# NE5532_TDA2030A.net
KiCad netlist of a schematic drawn in Altium Designer
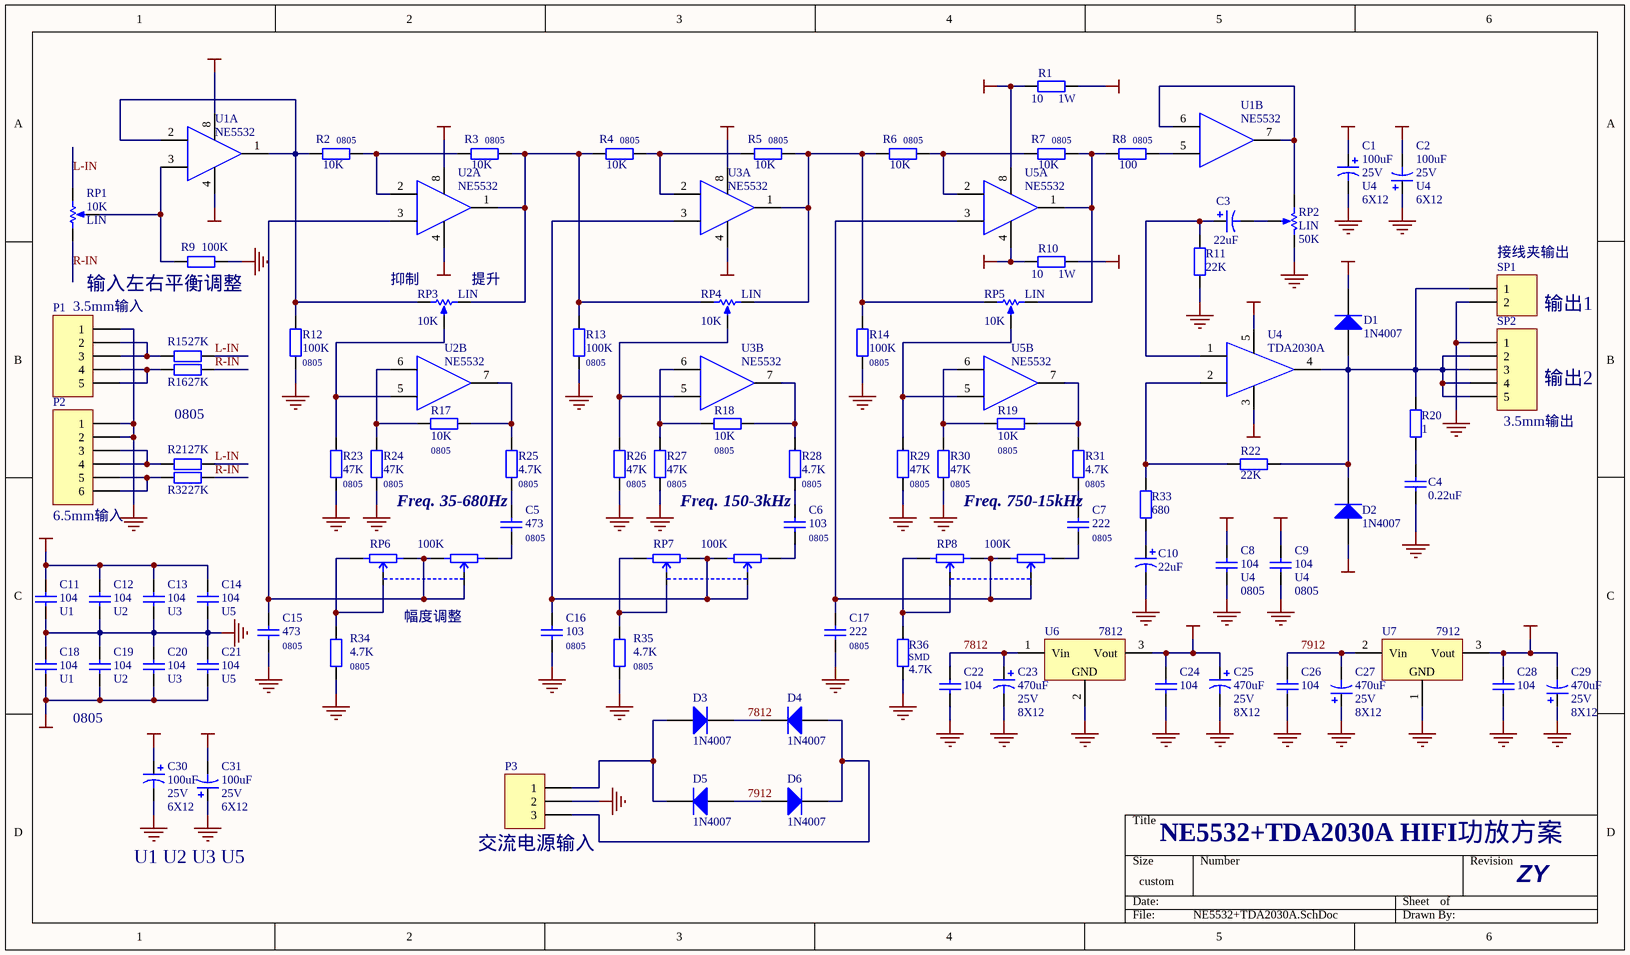
[diagram p0: NE5532+TDA2030A.SchDoc]

(export (version "E")
  (design (tool "Eeschema 10.0.6"))
  (components
    (comp (ref "C1")
      (value "U4")
      (footprint "C 6X12")
      (description "Polarized Capacitor (Radial)")
      (fields
        (field (name "PUBLISHED") "25V")
        (field (name "PUBLISHER") "6X12")
        (field (name "ALTIUM_VALUE") "100uF")
      )
      (libsource (lib "Miscellaneous Devices") (part "Cap Pol1"))
    )
    (comp (ref "C2")
      (value "U4")
      (footprint "C 6X12")
      (description "Polarized Capacitor (Radial)")
      (fields
        (field (name "PUBLISHED") "25V")
        (field (name "PUBLISHER") "6X12")
        (field (name "ALTIUM_VALUE") "100uF")
      )
      (libsource (lib "Miscellaneous Devices") (part "Cap Pol1"))
    )
    (comp (ref "C3")
      (value "22uF")
      (footprint "c1206")
      (description "Polarized Capacitor (Radial)")
      (fields (field (name "Comment") "Cap Pol1") (field (name "PUBLISHER") "Altium Limited"))
      (libsource (lib "Miscellaneous Devices") (part "Cap Pol1"))
    )
    (comp (ref "C4")
      (value "0.22uF")
      (footprint "RAD-0.1")
      (description "Capacitor")
      (fields (field (name "Comment") "Cap") (field (name "PUBLISHER") "Altium Limited"))
      (libsource (lib "Miscellaneous Devices") (part "Cap"))
    )
    (comp (ref "C5")
      (value "473")
      (footprint "c0805")
      (description "Capacitor")
      (fields (field (name "ALTIUM_VALUE") "0805") (field (name "PUBLISHER") "Altium Limited"))
      (libsource (lib "Miscellaneous Devices") (part "Cap"))
    )
    (comp (ref "C6")
      (value "103")
      (footprint "c0805")
      (description "Capacitor")
      (fields (field (name "ALTIUM_VALUE") "0805") (field (name "PUBLISHER") "Altium Limited"))
      (libsource (lib "Miscellaneous Devices") (part "Cap"))
    )
    (comp (ref "C7")
      (value "222")
      (footprint "c0805")
      (description "Capacitor")
      (fields (field (name "ALTIUM_VALUE") "0805") (field (name "PUBLISHER") "Altium Limited"))
      (libsource (lib "Miscellaneous Devices") (part "Cap"))
    )
    (comp (ref "C8")
      (value "U4")
      (footprint "c0805")
      (description "Capacitor")
      (fields (field (name "PUBLISHER") "0805") (field (name "ALTIUM_VALUE") "104"))
      (libsource (lib "Miscellaneous Devices") (part "Cap"))
    )
    (comp (ref "C9")
      (value "U4")
      (footprint "C0805")
      (description "Capacitor")
      (fields (field (name "PUBLISHER") "0805") (field (name "ALTIUM_VALUE") "104"))
      (libsource (lib "Miscellaneous Devices") (part "Cap"))
    )
    (comp (ref "C10")
      (value "22uF")
      (footprint "c1206")
      (description "Polarized Capacitor (Radial)")
      (fields (field (name "Comment") "Cap Pol1") (field (name "PUBLISHER") "Altium Limited"))
      (libsource (lib "Miscellaneous Devices") (part "Cap Pol1"))
    )
    (comp (ref "C11")
      (value "U1")
      (footprint "C0805")
      (description "Capacitor")
      (fields (field (name "ALTIUM_VALUE") "104") (field (name "PUBLISHER") "Altium Limited"))
      (libsource (lib "Miscellaneous Devices") (part "Cap"))
    )
    (comp (ref "C12")
      (value "U2")
      (footprint "C0805")
      (description "Capacitor")
      (fields (field (name "ALTIUM_VALUE") "104") (field (name "PUBLISHER") "Altium Limited"))
      (libsource (lib "Miscellaneous Devices") (part "Cap"))
    )
    (comp (ref "C13")
      (value "U3")
      (footprint "C0805")
      (description "Capacitor")
      (fields (field (name "ALTIUM_VALUE") "104") (field (name "PUBLISHER") "Altium Limited"))
      (libsource (lib "Miscellaneous Devices") (part "Cap"))
    )
    (comp (ref "C14")
      (value "U5")
      (footprint "C0805")
      (description "Capacitor")
      (fields (field (name "ALTIUM_VALUE") "104") (field (name "PUBLISHER") "Altium Limited"))
      (libsource (lib "Miscellaneous Devices") (part "Cap"))
    )
    (comp (ref "C15")
      (value "473")
      (footprint "c0805")
      (description "Capacitor")
      (fields (field (name "ALTIUM_VALUE") "0805") (field (name "PUBLISHER") "Altium Limited"))
      (libsource (lib "Miscellaneous Devices") (part "Cap"))
    )
    (comp (ref "C16")
      (value "103")
      (footprint "c0805")
      (description "Capacitor")
      (fields (field (name "ALTIUM_VALUE") "0805") (field (name "PUBLISHER") "Altium Limited"))
      (libsource (lib "Miscellaneous Devices") (part "Cap"))
    )
    (comp (ref "C17")
      (value "222")
      (footprint "c0805")
      (description "Capacitor")
      (fields (field (name "ALTIUM_VALUE") "0805") (field (name "PUBLISHER") "Altium Limited"))
      (libsource (lib "Miscellaneous Devices") (part "Cap"))
    )
    (comp (ref "C18")
      (value "U1")
      (footprint "C0805")
      (description "Capacitor")
      (fields (field (name "ALTIUM_VALUE") "104") (field (name "PUBLISHER") "Altium Limited"))
      (libsource (lib "Miscellaneous Devices") (part "Cap"))
    )
    (comp (ref "C19")
      (value "U2")
      (footprint "C0805")
      (description "Capacitor")
      (fields (field (name "ALTIUM_VALUE") "104") (field (name "PUBLISHER") "Altium Limited"))
      (libsource (lib "Miscellaneous Devices") (part "Cap"))
    )
    (comp (ref "C20")
      (value "U3")
      (footprint "C0805")
      (description "Capacitor")
      (fields (field (name "ALTIUM_VALUE") "104") (field (name "PUBLISHER") "Altium Limited"))
      (libsource (lib "Miscellaneous Devices") (part "Cap"))
    )
    (comp (ref "C21")
      (value "U5")
      (footprint "C0805")
      (description "Capacitor")
      (fields (field (name "ALTIUM_VALUE") "104") (field (name "PUBLISHER") "Altium Limited"))
      (libsource (lib "Miscellaneous Devices") (part "Cap"))
    )
    (comp (ref "C22")
      (value "104")
      (footprint "RAD-0.1")
      (description "Capacitor")
      (fields (field (name "Comment") "U4") (field (name "PUBLISHER") "Altium Limited"))
      (libsource (lib "Miscellaneous Devices") (part "Cap"))
    )
    (comp (ref "C23")
      (value "25V")
      (footprint "C 8X12")
      (description "Polarized Capacitor (Radial)")
      (fields
        (field (name "ALTIUM_VALUE") "470uF")
        (field (name "ALTIUM_UNNAMED_1") "8X12")
        (field (name "PUBLISHER") "Altium Limited")
      )
      (libsource (lib "Miscellaneous Devices") (part "Cap Pol1"))
    )
    (comp (ref "C24")
      (value "104")
      (footprint "RAD-0.1")
      (description "Capacitor")
      (fields (field (name "Comment") "U4") (field (name "PUBLISHER") "Altium Limited"))
      (libsource (lib "Miscellaneous Devices") (part "Cap"))
    )
    (comp (ref "C25")
      (value "25V")
      (footprint "C 8X12")
      (description "Polarized Capacitor (Radial)")
      (fields
        (field (name "ALTIUM_VALUE") "470uF")
        (field (name "ALTIUM_UNNAMED_1") "8X12")
        (field (name "PUBLISHER") "Altium Limited")
      )
      (libsource (lib "Miscellaneous Devices") (part "Cap Pol1"))
    )
    (comp (ref "C26")
      (value "104")
      (footprint "RAD-0.1")
      (description "Capacitor")
      (fields (field (name "Comment") "U4") (field (name "PUBLISHER") "Altium Limited"))
      (libsource (lib "Miscellaneous Devices") (part "Cap"))
    )
    (comp (ref "C27")
      (value "25V")
      (footprint "C 8X12")
      (description "Polarized Capacitor (Radial)")
      (fields
        (field (name "ALTIUM_VALUE") "470uF")
        (field (name "ALTIUM_UNNAMED_1") "8X12")
        (field (name "PUBLISHER") "Altium Limited")
      )
      (libsource (lib "Miscellaneous Devices") (part "Cap Pol1"))
    )
    (comp (ref "C28")
      (value "104")
      (footprint "RAD-0.1")
      (description "Capacitor")
      (fields (field (name "Comment") "U4") (field (name "PUBLISHER") "Altium Limited"))
      (libsource (lib "Miscellaneous Devices") (part "Cap"))
    )
    (comp (ref "C29")
      (value "25V")
      (footprint "C 8X12")
      (description "Polarized Capacitor (Radial)")
      (fields
        (field (name "ALTIUM_VALUE") "470uF")
        (field (name "ALTIUM_UNNAMED_1") "8X12")
        (field (name "PUBLISHER") "Altium Limited")
      )
      (libsource (lib "Miscellaneous Devices") (part "Cap Pol1"))
    )
    (comp (ref "C30")
      (value "25V")
      (footprint "C 6X12")
      (description "Polarized Capacitor (Radial)")
      (fields (field (name "PUBLISHER") "6X12") (field (name "ALTIUM_VALUE") "100uF"))
      (libsource (lib "Miscellaneous Devices") (part "Cap Pol1"))
    )
    (comp (ref "C31")
      (value "25V")
      (footprint "C 6X12")
      (description "Polarized Capacitor (Radial)")
      (fields (field (name "PUBLISHER") "6X12") (field (name "ALTIUM_VALUE") "100uF"))
      (libsource (lib "Miscellaneous Devices") (part "Cap Pol1"))
    )
    (comp (ref "D1")
      (value "1N4007")
      (footprint "DIO10.46-5.3x2.8")
      (description "1 Amp General Purpose Rectifier")
      (fields (field (name "PUBLISHER") "Altium Limited"))
      (libsource (lib "Miscellaneous Devices") (part "Diode 1N4007"))
    )
    (comp (ref "D2")
      (value "1N4007")
      (footprint "DIO10.46-5.3x2.8")
      (description "1 Amp General Purpose Rectifier")
      (fields (field (name "PUBLISHER") "Altium Limited"))
      (libsource (lib "Miscellaneous Devices") (part "Diode 1N4007"))
    )
    (comp (ref "D3")
      (value "1N4007")
      (footprint "DIO10.46-5.3x2.8")
      (description "1 Amp General Purpose Rectifier")
      (fields (field (name "PUBLISHER") "Altium Limited"))
      (libsource (lib "Miscellaneous Devices") (part "Diode 1N4007"))
    )
    (comp (ref "D4")
      (value "1N4007")
      (footprint "DIO10.46-5.3x2.8")
      (description "1 Amp General Purpose Rectifier")
      (fields (field (name "PUBLISHER") "Altium Limited"))
      (libsource (lib "Miscellaneous Devices") (part "Diode 1N4007"))
    )
    (comp (ref "D5")
      (value "1N4007")
      (footprint "DIO10.46-5.3x2.8")
      (description "1 Amp General Purpose Rectifier")
      (fields (field (name "PUBLISHER") "Altium Limited"))
      (libsource (lib "Miscellaneous Devices") (part "Diode 1N4007"))
    )
    (comp (ref "D6")
      (value "1N4007")
      (footprint "DIO10.46-5.3x2.8")
      (description "1 Amp General Purpose Rectifier")
      (fields (field (name "PUBLISHER") "Altium Limited"))
      (libsource (lib "Miscellaneous Devices") (part "Diode 1N4007"))
    )
    (comp (ref "P1")
      (value "Header 5")
      (footprint "3.5MM")
      (description "Header, 5-Pin")
      (fields (field (name "PUBLISHER") "Altium Limited"))
      (libsource (lib "") (part "Header 5_1"))
    )
    (comp (ref "P2")
      (value "Header 6")
      (footprint "6.5MM")
      (description "Header, 6-Pin")
      (fields (field (name "PUBLISHER") "Altium Limited"))
      (libsource (lib "Miscellaneous Connectors") (part "Header 6"))
    )
    (comp (ref "P3")
      (value "Header 3")
      (footprint "h3")
      (description "Header, 3-Pin")
      (fields (field (name "PUBLISHER") "Altium Limited"))
      (libsource (lib "Miscellaneous Connectors") (part "Header 3"))
    )
    (comp (ref "R1")
      (value "1W")
      (footprint "AXIAL-0.6")
      (description "Resistor")
      (fields (field (name "ALTIUM_VALUE") "10") (field (name "PUBLISHER") "Altium Limited"))
      (libsource (lib "Miscellaneous Devices") (part "Res2"))
    )
    (comp (ref "R2")
      (value "0805")
      (footprint "R0805")
      (description "Resistor")
      (fields (field (name "ALTIUM_VALUE") "10K") (field (name "PUBLISHER") "Altium Limited"))
      (libsource (lib "Miscellaneous Devices") (part "Res2"))
    )
    (comp (ref "R3")
      (value "0805")
      (footprint "R0805")
      (description "Resistor")
      (fields (field (name "ALTIUM_VALUE") "10K") (field (name "PUBLISHER") "Altium Limited"))
      (libsource (lib "Miscellaneous Devices") (part "Res2"))
    )
    (comp (ref "R4")
      (value "0805")
      (footprint "R0805")
      (description "Resistor")
      (fields (field (name "ALTIUM_VALUE") "10K") (field (name "PUBLISHER") "Altium Limited"))
      (libsource (lib "Miscellaneous Devices") (part "Res2"))
    )
    (comp (ref "R5")
      (value "0805")
      (footprint "R0805")
      (description "Resistor")
      (fields (field (name "ALTIUM_VALUE") "10K") (field (name "PUBLISHER") "Altium Limited"))
      (libsource (lib "Miscellaneous Devices") (part "Res2"))
    )
    (comp (ref "R6")
      (value "0805")
      (footprint "R0805")
      (description "Resistor")
      (fields (field (name "ALTIUM_VALUE") "10K") (field (name "PUBLISHER") "Altium Limited"))
      (libsource (lib "Miscellaneous Devices") (part "Res2"))
    )
    (comp (ref "R7")
      (value "0805")
      (footprint "R0805")
      (description "Resistor")
      (fields (field (name "ALTIUM_VALUE") "10K") (field (name "PUBLISHER") "Altium Limited"))
      (libsource (lib "Miscellaneous Devices") (part "Res2"))
    )
    (comp (ref "R8")
      (value "0805")
      (footprint "R0805")
      (description "Resistor")
      (fields (field (name "ALTIUM_VALUE") "100") (field (name "PUBLISHER") "Altium Limited"))
      (libsource (lib "Miscellaneous Devices") (part "Res2"))
    )
    (comp (ref "R9")
      (value "100K")
      (footprint "R0805")
      (description "Resistor")
      (fields (field (name "Comment") "0805") (field (name "PUBLISHER") "Altium Limited"))
      (libsource (lib "") (part "Res2_3"))
    )
    (comp (ref "R10")
      (value "1W")
      (footprint "AXIAL-0.6")
      (description "Resistor")
      (fields (field (name "ALTIUM_VALUE") "10") (field (name "PUBLISHER") "Altium Limited"))
      (libsource (lib "Miscellaneous Devices") (part "Res2"))
    )
    (comp (ref "R11")
      (value "22K")
      (footprint "AXIAL-0.4")
      (description "Resistor")
      (fields (field (name "Comment") "Res2") (field (name "PUBLISHER") "Altium Limited"))
      (libsource (lib "") (part "Res2_2"))
    )
    (comp (ref "R12")
      (value "0805")
      (footprint "R0805")
      (description "Resistor")
      (fields (field (name "ALTIUM_VALUE") "100K") (field (name "PUBLISHER") "Altium Limited"))
      (libsource (lib "") (part "Res2_2"))
    )
    (comp (ref "R13")
      (value "0805")
      (footprint "R0805")
      (description "Resistor")
      (fields (field (name "ALTIUM_VALUE") "100K") (field (name "PUBLISHER") "Altium Limited"))
      (libsource (lib "") (part "Res2_2"))
    )
    (comp (ref "R14")
      (value "0805")
      (footprint "R0805")
      (description "Resistor")
      (fields (field (name "ALTIUM_VALUE") "100K") (field (name "PUBLISHER") "Altium Limited"))
      (libsource (lib "") (part "Res2_2"))
    )
    (comp (ref "R15")
      (value "27K")
      (footprint "R0805")
      (description "Resistor")
      (fields (field (name "Comment") "0805") (field (name "PUBLISHER") "Altium Limited"))
      (libsource (lib "") (part "Res2_3"))
    )
    (comp (ref "R16")
      (value "27K")
      (footprint "R0805")
      (description "Resistor")
      (fields (field (name "Comment") "0805") (field (name "PUBLISHER") "Altium Limited"))
      (libsource (lib "") (part "Res2_3"))
    )
    (comp (ref "R17")
      (value "0805")
      (footprint "R0805")
      (description "Resistor")
      (fields (field (name "ALTIUM_VALUE") "10K") (field (name "PUBLISHER") "Altium Limited"))
      (libsource (lib "") (part "Res2_3"))
    )
    (comp (ref "R18")
      (value "0805")
      (footprint "R0805")
      (description "Resistor")
      (fields (field (name "ALTIUM_VALUE") "10K") (field (name "PUBLISHER") "Altium Limited"))
      (libsource (lib "") (part "Res2_3"))
    )
    (comp (ref "R19")
      (value "0805")
      (footprint "R0805")
      (description "Resistor")
      (fields (field (name "ALTIUM_VALUE") "10K") (field (name "PUBLISHER") "Altium Limited"))
      (libsource (lib "") (part "Res2_3"))
    )
    (comp (ref "R20")
      (value "1")
      (footprint "AXIAL-0.4")
      (description "Resistor")
      (fields (field (name "Comment") "Res2") (field (name "PUBLISHER") "Altium Limited"))
      (libsource (lib "") (part "Res2_2"))
    )
    (comp (ref "R21")
      (value "27K")
      (footprint "R0805")
      (description "Resistor")
      (fields (field (name "Comment") "0805") (field (name "PUBLISHER") "Altium Limited"))
      (libsource (lib "") (part "Res2_3"))
    )
    (comp (ref "R22")
      (value "22K")
      (footprint "AXIAL-0.4")
      (description "Resistor")
      (fields (field (name "Comment") "Res2") (field (name "PUBLISHER") "Altium Limited"))
      (libsource (lib "") (part "Res2_3"))
    )
    (comp (ref "R23")
      (value "0805")
      (footprint "R0805")
      (description "Resistor")
      (fields (field (name "ALTIUM_VALUE") "47K") (field (name "PUBLISHER") "Altium Limited"))
      (libsource (lib "") (part "Res2_2"))
    )
    (comp (ref "R24")
      (value "0805")
      (footprint "R0805")
      (description "Resistor")
      (fields (field (name "ALTIUM_VALUE") "47K") (field (name "PUBLISHER") "Altium Limited"))
      (libsource (lib "") (part "Res2_2"))
    )
    (comp (ref "R25")
      (value "0805")
      (footprint "R0805")
      (description "Resistor")
      (fields (field (name "ALTIUM_VALUE") "4.7K") (field (name "PUBLISHER") "Altium Limited"))
      (libsource (lib "") (part "Res2_1"))
    )
    (comp (ref "R26")
      (value "0805")
      (footprint "R0805")
      (description "Resistor")
      (fields (field (name "ALTIUM_VALUE") "47K") (field (name "PUBLISHER") "Altium Limited"))
      (libsource (lib "") (part "Res2_2"))
    )
    (comp (ref "R27")
      (value "0805")
      (footprint "R0805")
      (description "Resistor")
      (fields (field (name "ALTIUM_VALUE") "47K") (field (name "PUBLISHER") "Altium Limited"))
      (libsource (lib "") (part "Res2_2"))
    )
    (comp (ref "R28")
      (value "0805")
      (footprint "R0805")
      (description "Resistor")
      (fields (field (name "ALTIUM_VALUE") "4.7K") (field (name "PUBLISHER") "Altium Limited"))
      (libsource (lib "") (part "Res2_1"))
    )
    (comp (ref "R29")
      (value "0805")
      (footprint "R0805")
      (description "Resistor")
      (fields (field (name "ALTIUM_VALUE") "47K") (field (name "PUBLISHER") "Altium Limited"))
      (libsource (lib "") (part "Res2_2"))
    )
    (comp (ref "R30")
      (value "0805")
      (footprint "R0805")
      (description "Resistor")
      (fields (field (name "ALTIUM_VALUE") "47K") (field (name "PUBLISHER") "Altium Limited"))
      (libsource (lib "") (part "Res2_2"))
    )
    (comp (ref "R31")
      (value "0805")
      (footprint "R0805")
      (description "Resistor")
      (fields (field (name "ALTIUM_VALUE") "4.7K") (field (name "PUBLISHER") "Altium Limited"))
      (libsource (lib "") (part "Res2_1"))
    )
    (comp (ref "R32")
      (value "27K")
      (footprint "R0805")
      (description "Resistor")
      (fields (field (name "Comment") "0805") (field (name "PUBLISHER") "Altium Limited"))
      (libsource (lib "") (part "Res2_3"))
    )
    (comp (ref "R33")
      (value "680")
      (footprint "AXIAL-0.4")
      (description "Resistor")
      (fields (field (name "Comment") "Res2") (field (name "PUBLISHER") "Altium Limited"))
      (libsource (lib "") (part "Res2_2"))
    )
    (comp (ref "R34")
      (value "0805")
      (footprint "R0805")
      (description "Resistor")
      (fields (field (name "ALTIUM_VALUE") "4.7K") (field (name "PUBLISHER") "Altium Limited"))
      (libsource (lib "") (part "Res2_1"))
    )
    (comp (ref "R35")
      (value "0805")
      (footprint "R0805")
      (description "Resistor")
      (fields (field (name "ALTIUM_VALUE") "4.7K") (field (name "PUBLISHER") "Altium Limited"))
      (libsource (lib "") (part "Res2_1"))
    )
    (comp (ref "R36")
      (value "SMD")
      (footprint "R0805")
      (description "Resistor")
      (fields (field (name "ALTIUM_VALUE") "4.7K") (field (name "PUBLISHER") "Altium Limited"))
      (libsource (lib "") (part "Res2_1"))
    )
    (comp (ref "RP1")
      (value "LIN")
      (footprint "RP-1")
      (description "Potentiometer")
      (fields (field (name "ALTIUM_VALUE") "10K") (field (name "PUBLISHER") "Altium Limited"))
      (libsource (lib "Miscellaneous Devices") (part "RPot"))
    )
    (comp (ref "RP2")
      (value "LIN")
      (footprint "RP-1")
      (description "Potentiometer")
      (fields (field (name "ALTIUM_VALUE") "50K") (field (name "PUBLISHER") "Altium Limited"))
      (libsource (lib "Miscellaneous Devices") (part "RPot"))
    )
    (comp (ref "RP3")
      (value "LIN")
      (footprint "VR5")
      (description "Potentiometer")
      (fields (field (name "ALTIUM_VALUE") "10K") (field (name "PUBLISHER") "Altium Limited"))
      (libsource (lib "Miscellaneous Devices") (part "RPot"))
    )
    (comp (ref "RP4")
      (value "LIN")
      (footprint "VR5")
      (description "Potentiometer")
      (fields (field (name "ALTIUM_VALUE") "10K") (field (name "PUBLISHER") "Altium Limited"))
      (libsource (lib "Miscellaneous Devices") (part "RPot"))
    )
    (comp (ref "RP5")
      (value "LIN")
      (footprint "VR5")
      (description "Potentiometer")
      (fields (field (name "ALTIUM_VALUE") "10K") (field (name "PUBLISHER") "Altium Limited"))
      (libsource (lib "Miscellaneous Devices") (part "RPot"))
    )
    (comp (ref "RP6") (value "100K") (footprint "RP-2") (libsource (lib "NE5532+TDA2030A") (part "RP-2")))
    (comp (ref "RP7") (value "100K") (footprint "RP-2") (libsource (lib "NE5532+TDA2030A") (part "RP-2")))
    (comp (ref "RP8") (value "100K") (footprint "RP-2") (libsource (lib "NE5532+TDA2030A") (part "RP-2")))
    (comp (ref "SP1")
      (value "Header 2")
      (footprint "H2")
      (description "Header, 2-Pin")
      (fields (field (name "PUBLISHER") "Altium Limited"))
      (libsource (lib "Miscellaneous Connectors") (part "Header 2"))
    )
    (comp (ref "SP2")
      (value "Header 5")
      (footprint "3.5MM")
      (description "Header, 5-Pin")
      (fields (field (name "PUBLISHER") "Altium Limited"))
      (libsource (lib "Miscellaneous Connectors") (part "Header 5"))
    )
    (comp (ref "U1") (value "NE5532") (footprint "DIP-8") (libsource (lib "NE5532+TDA2030A") (part "NE5532")))
    (comp (ref "U2") (value "NE5532") (footprint "DIP-8") (libsource (lib "NE5532+TDA2030A") (part "NE5532")))
    (comp (ref "U3") (value "NE5532") (footprint "DIP-8") (libsource (lib "NE5532+TDA2030A") (part "NE5532")))
    (comp (ref "U4")
      (value "TDA2030A")
      (footprint "TDA2030")
      (libsource (lib "NE5532+TDA2030A") (part "TDA2030A"))
    )
    (comp (ref "U5") (value "NE5532") (footprint "DIP-8") (libsource (lib "NE5532+TDA2030A") (part "NE5532")))
    (comp (ref "U6") (value "7812") (footprint "TO-220") (libsource (lib "NE5532+TDA2030A") (part "7812")))
    (comp (ref "U7") (value "7912") (footprint "TO-220") (libsource (lib "NE5532+TDA2030A") (part "7912")))
  )
  (nets
    (net (code "1") (name "+12V") (class "Default")
      (node (ref "C1") (pin "1") (pinfunction "1_1") (pintype "passive"))
      (node (ref "C24") (pin "1") (pinfunction "1_1") (pintype "passive"))
      (node (ref "C25") (pin "1") (pinfunction "1_1") (pintype "passive"))
      (node (ref "C8") (pin "1") (pinfunction "1_1") (pintype "passive"))
      (node (ref "D1") (pin "2") (pinfunction "K_2") (pintype "passive"))
      (node (ref "R1") (pin "2") (pinfunction "2_2") (pintype "passive"))
      (node (ref "U4") (pin "5") (pinfunction "5_5") (pintype "passive"))
      (node (ref "U6") (pin "3") (pinfunction "Vout_3") (pintype "passive"))
    )
    (net (code "2") (name "-12V") (class "Default")
      (node (ref "C2") (pin "2") (pinfunction "2_2") (pintype "passive"))
      (node (ref "C28") (pin "1") (pinfunction "1_1") (pintype "passive"))
      (node (ref "C29") (pin "2") (pinfunction "2_2") (pintype "passive"))
      (node (ref "C9") (pin "1") (pinfunction "1_1") (pintype "passive"))
      (node (ref "D2") (pin "1") (pinfunction "A_1") (pintype "passive"))
      (node (ref "R10") (pin "2") (pinfunction "2_2") (pintype "passive"))
      (node (ref "U4") (pin "3") (pinfunction "3_3") (pintype "passive"))
      (node (ref "U7") (pin "3") (pinfunction "Vout_3") (pintype "passive"))
    )
    (net (code "3") (name "/7812") (class "Default")
      (node (ref "C22") (pin "1") (pinfunction "1_1") (pintype "passive"))
      (node (ref "C23") (pin "1") (pinfunction "1_1") (pintype "passive"))
      (node (ref "D3") (pin "2") (pinfunction "K_2") (pintype "passive"))
      (node (ref "D4") (pin "2") (pinfunction "K_2") (pintype "passive"))
      (node (ref "U6") (pin "1") (pinfunction "Vin_1") (pintype "passive"))
    )
    (net (code "4") (name "/7912") (class "Default")
      (node (ref "C26") (pin "1") (pinfunction "1_1") (pintype "passive"))
      (node (ref "C27") (pin "2") (pinfunction "2_2") (pintype "passive"))
      (node (ref "D5") (pin "1") (pinfunction "A_1") (pintype "passive"))
      (node (ref "D6") (pin "1") (pinfunction "A_1") (pintype "passive"))
      (node (ref "U7") (pin "2") (pinfunction "Vin_2") (pintype "passive"))
    )
    (net (code "5") (name "/L-IN") (class "Default")
      (node (ref "R15") (pin "1") (pinfunction "1_1") (pintype "passive"))
      (node (ref "R21") (pin "1") (pinfunction "1_1") (pintype "passive"))
      (node (ref "RP1") (pin "2") (pinfunction "BOT_2") (pintype "passive"))
    )
    (net (code "6") (name "/R-IN") (class "Default")
      (node (ref "R16") (pin "1") (pinfunction "1_1") (pintype "passive"))
      (node (ref "R32") (pin "1") (pinfunction "1_1") (pintype "passive"))
      (node (ref "RP1") (pin "1") (pinfunction "TOP_1") (pintype "passive"))
    )
    (net (code "7") (name "GND") (class "Default")
      (node (ref "C1") (pin "2") (pinfunction "2_2") (pintype "passive"))
      (node (ref "C10") (pin "2") (pinfunction "2_2") (pintype "passive"))
      (node (ref "C11") (pin "1") (pinfunction "1_1") (pintype "passive"))
      (node (ref "C12") (pin "1") (pinfunction "1_1") (pintype "passive"))
      (node (ref "C13") (pin "1") (pinfunction "1_1") (pintype "passive"))
      (node (ref "C14") (pin "1") (pinfunction "1_1") (pintype "passive"))
      (node (ref "C15") (pin "1") (pinfunction "1_1") (pintype "passive"))
      (node (ref "C16") (pin "1") (pinfunction "1_1") (pintype "passive"))
      (node (ref "C17") (pin "1") (pinfunction "1_1") (pintype "passive"))
      (node (ref "C18") (pin "2") (pinfunction "2_2") (pintype "passive"))
      (node (ref "C19") (pin "2") (pinfunction "2_2") (pintype "passive"))
      (node (ref "C2") (pin "1") (pinfunction "1_1") (pintype "passive"))
      (node (ref "C20") (pin "2") (pinfunction "2_2") (pintype "passive"))
      (node (ref "C21") (pin "2") (pinfunction "2_2") (pintype "passive"))
      (node (ref "C22") (pin "2") (pinfunction "2_2") (pintype "passive"))
      (node (ref "C23") (pin "2") (pinfunction "2_2") (pintype "passive"))
      (node (ref "C24") (pin "2") (pinfunction "2_2") (pintype "passive"))
      (node (ref "C25") (pin "2") (pinfunction "2_2") (pintype "passive"))
      (node (ref "C26") (pin "2") (pinfunction "2_2") (pintype "passive"))
      (node (ref "C27") (pin "1") (pinfunction "1_1") (pintype "passive"))
      (node (ref "C28") (pin "2") (pinfunction "2_2") (pintype "passive"))
      (node (ref "C29") (pin "1") (pinfunction "1_1") (pintype "passive"))
      (node (ref "C30") (pin "2") (pinfunction "2_2") (pintype "passive"))
      (node (ref "C31") (pin "1") (pinfunction "1_1") (pintype "passive"))
      (node (ref "C4") (pin "2") (pinfunction "2_2") (pintype "passive"))
      (node (ref "C8") (pin "2") (pinfunction "2_2") (pintype "passive"))
      (node (ref "C9") (pin "2") (pinfunction "2_2") (pintype "passive"))
      (node (ref "P1") (pin "1") (pinfunction "1_1") (pintype "passive"))
      (node (ref "P2") (pin "1") (pinfunction "1_1") (pintype "passive"))
      (node (ref "P2") (pin "2") (pinfunction "2_2") (pintype "passive"))
      (node (ref "P3") (pin "2") (pinfunction "2_2") (pintype "passive"))
      (node (ref "R11") (pin "1") (pinfunction "1_1") (pintype "passive"))
      (node (ref "R12") (pin "1") (pinfunction "1_1") (pintype "passive"))
      (node (ref "R13") (pin "1") (pinfunction "1_1") (pintype "passive"))
      (node (ref "R14") (pin "1") (pinfunction "1_1") (pintype "passive"))
      (node (ref "R23") (pin "1") (pinfunction "1_1") (pintype "passive"))
      (node (ref "R24") (pin "1") (pinfunction "1_1") (pintype "passive"))
      (node (ref "R26") (pin "1") (pinfunction "1_1") (pintype "passive"))
      (node (ref "R27") (pin "1") (pinfunction "1_1") (pintype "passive"))
      (node (ref "R29") (pin "1") (pinfunction "1_1") (pintype "passive"))
      (node (ref "R30") (pin "1") (pinfunction "1_1") (pintype "passive"))
      (node (ref "R34") (pin "2") (pinfunction "2_2") (pintype "passive"))
      (node (ref "R35") (pin "2") (pinfunction "2_2") (pintype "passive"))
      (node (ref "R36") (pin "2") (pinfunction "2_2") (pintype "passive"))
      (node (ref "R9") (pin "1") (pinfunction "1_1") (pintype "passive"))
      (node (ref "RP2") (pin "1") (pinfunction "TOP_1") (pintype "passive"))
      (node (ref "SP1") (pin "2") (pinfunction "2_2") (pintype "passive"))
      (node (ref "SP2") (pin "1") (pinfunction "1_1") (pintype "passive"))
      (node (ref "U6") (pin "2") (pinfunction "GND_2") (pintype "passive"))
      (node (ref "U7") (pin "1") (pinfunction "GND_1") (pintype "passive"))
    )
    (net (code "8") (name "Net-(C3-Pad1)") (class "Default")
      (node (ref "C3") (pin "1") (pinfunction "1_1") (pintype "passive"))
      (node (ref "R11") (pin "2") (pinfunction "2_2") (pintype "passive"))
      (node (ref "U4") (pin "1") (pinfunction "1_1") (pintype "passive"))
    )
    (net (code "9") (name "Net-(C4-Pad1)") (class "Default")
      (node (ref "C4") (pin "1") (pinfunction "1_1") (pintype "passive"))
      (node (ref "R20") (pin "1") (pinfunction "1_1") (pintype "passive"))
    )
    (net (code "10") (name "Net-(C5-Pad1)") (class "Default")
      (node (ref "C5") (pin "1") (pinfunction "1_1") (pintype "passive"))
      (node (ref "RP6") (pin "5") (pinfunction "5_5") (pintype "passive"))
    )
    (net (code "11") (name "Net-(C5-Pad2)") (class "Default")
      (node (ref "C5") (pin "2") (pinfunction "2_2") (pintype "passive"))
      (node (ref "R25") (pin "2") (pinfunction "2_2") (pintype "passive"))
    )
    (net (code "12") (name "Net-(C6-Pad1)") (class "Default")
      (node (ref "C6") (pin "1") (pinfunction "1_1") (pintype "passive"))
      (node (ref "RP7") (pin "5") (pinfunction "5_5") (pintype "passive"))
    )
    (net (code "13") (name "Net-(C6-Pad2)") (class "Default")
      (node (ref "C6") (pin "2") (pinfunction "2_2") (pintype "passive"))
      (node (ref "R28") (pin "2") (pinfunction "2_2") (pintype "passive"))
    )
    (net (code "14") (name "Net-(C7-Pad1)") (class "Default")
      (node (ref "C7") (pin "1") (pinfunction "1_1") (pintype "passive"))
      (node (ref "RP8") (pin "5") (pinfunction "5_5") (pintype "passive"))
    )
    (net (code "15") (name "Net-(C7-Pad2)") (class "Default")
      (node (ref "C7") (pin "2") (pinfunction "2_2") (pintype "passive"))
      (node (ref "R31") (pin "2") (pinfunction "2_2") (pintype "passive"))
    )
    (net (code "16") (name "Net-(C10-Pad1)") (class "Default")
      (node (ref "C10") (pin "1") (pinfunction "1_1") (pintype "passive"))
      (node (ref "R33") (pin "1") (pinfunction "1_1") (pintype "passive"))
    )
    (net (code "17") (name "Net-(D1-A)") (class "Default")
      (node (ref "D1") (pin "1") (pinfunction "A_1") (pintype "passive"))
      (node (ref "D2") (pin "2") (pinfunction "K_2") (pintype "passive"))
      (node (ref "R20") (pin "2") (pinfunction "2_2") (pintype "passive"))
      (node (ref "R22") (pin "1") (pinfunction "1_1") (pintype "passive"))
      (node (ref "SP1") (pin "1") (pinfunction "1_1") (pintype "passive"))
      (node (ref "SP2") (pin "2") (pinfunction "2_2") (pintype "passive"))
      (node (ref "SP2") (pin "3") (pinfunction "3_3") (pintype "passive"))
      (node (ref "SP2") (pin "4") (pinfunction "4_4") (pintype "passive"))
      (node (ref "SP2") (pin "5") (pinfunction "5_5") (pintype "passive"))
      (node (ref "U4") (pin "4") (pinfunction "4_4") (pintype "passive"))
    )
    (net (code "18") (name "Net-(D3-A)") (class "Default")
      (node (ref "D3") (pin "1") (pinfunction "A_1") (pintype "passive"))
      (node (ref "D5") (pin "2") (pinfunction "K_2") (pintype "passive"))
      (node (ref "P3") (pin "1") (pinfunction "1_1") (pintype "passive"))
    )
    (net (code "19") (name "Net-(D4-A)") (class "Default")
      (node (ref "D4") (pin "1") (pinfunction "A_1") (pintype "passive"))
      (node (ref "D6") (pin "2") (pinfunction "K_2") (pintype "passive"))
      (node (ref "P3") (pin "3") (pinfunction "3_3") (pintype "passive"))
    )
    (net (code "20") (name "Net-(P1-Pad2)") (class "Default")
      (node (ref "P1") (pin "2") (pinfunction "2_2") (pintype "passive"))
      (node (ref "P1") (pin "3") (pinfunction "3_3") (pintype "passive"))
      (node (ref "R15") (pin "2") (pinfunction "2_2") (pintype "passive"))
    )
    (net (code "21") (name "Net-(P1-Pad4)") (class "Default")
      (node (ref "P1") (pin "4") (pinfunction "4_4") (pintype "passive"))
      (node (ref "P1") (pin "5") (pinfunction "5_5") (pintype "passive"))
      (node (ref "R16") (pin "2") (pinfunction "2_2") (pintype "passive"))
    )
    (net (code "22") (name "Net-(P2-Pad3)") (class "Default")
      (node (ref "P2") (pin "3") (pinfunction "3_3") (pintype "passive"))
      (node (ref "P2") (pin "4") (pinfunction "4_4") (pintype "passive"))
      (node (ref "R21") (pin "2") (pinfunction "2_2") (pintype "passive"))
    )
    (net (code "23") (name "Net-(P2-Pad5)") (class "Default")
      (node (ref "P2") (pin "5") (pinfunction "5_5") (pintype "passive"))
      (node (ref "P2") (pin "6") (pinfunction "6_6") (pintype "passive"))
      (node (ref "R32") (pin "2") (pinfunction "2_2") (pintype "passive"))
    )
    (net (code "24") (name "Net-(R22-Pad2)") (class "Default")
      (node (ref "R22") (pin "2") (pinfunction "2_2") (pintype "passive"))
      (node (ref "R33") (pin "2") (pinfunction "2_2") (pintype "passive"))
      (node (ref "U4") (pin "2") (pinfunction "2_2") (pintype "passive"))
    )
    (net (code "25") (name "Net-(R34-Pad1)") (class "Default")
      (node (ref "R34") (pin "1") (pinfunction "1_1") (pintype "passive"))
      (node (ref "RP6") (pin "1") (pinfunction "1_1") (pintype "passive"))
      (node (ref "RP6") (pin "3") (pinfunction "3_3") (pintype "passive"))
    )
    (net (code "26") (name "Net-(R35-Pad1)") (class "Default")
      (node (ref "R35") (pin "1") (pinfunction "1_1") (pintype "passive"))
      (node (ref "RP7") (pin "1") (pinfunction "1_1") (pintype "passive"))
      (node (ref "RP7") (pin "3") (pinfunction "3_3") (pintype "passive"))
    )
    (net (code "27") (name "Net-(R36-Pad1)") (class "Default")
      (node (ref "R36") (pin "1") (pinfunction "1_1") (pintype "passive"))
      (node (ref "RP8") (pin "1") (pinfunction "1_1") (pintype "passive"))
      (node (ref "RP8") (pin "3") (pinfunction "3_3") (pintype "passive"))
    )
    (net (code "28") (name "Net-(RP1-TAP)") (class "Default")
      (node (ref "R9") (pin "2") (pinfunction "2_2") (pintype "passive"))
      (node (ref "RP1") (pin "3") (pinfunction "TAP_3") (pintype "passive"))
      (node (ref "U1") (pin "3") (pinfunction "IN+_3") (pintype "passive"))
    )
    (net (code "29") (name "Net-(RP2-BOT)") (class "Default")
      (node (ref "RP2") (pin "2") (pinfunction "BOT_2") (pintype "passive"))
      (node (ref "U1") (pin "6") (pinfunction "IN-_6") (pintype "passive"))
      (node (ref "U1") (pin "7") (pinfunction "OUT2_7") (pintype "passive"))
    )
    (net (code "30") (name "Net-(RP2-TAP)") (class "Default")
      (node (ref "C3") (pin "2") (pinfunction "2_2") (pintype "passive"))
      (node (ref "RP2") (pin "3") (pinfunction "TAP_3") (pintype "passive"))
    )
    (net (code "31") (name "Net-(RP3-BOT)") (class "Default")
      (node (ref "R13") (pin "2") (pinfunction "2_2") (pintype "passive"))
      (node (ref "R3") (pin "2") (pinfunction "2_2") (pintype "passive"))
      (node (ref "R4") (pin "1") (pinfunction "1_1") (pintype "passive"))
      (node (ref "RP3") (pin "2") (pinfunction "BOT_2") (pintype "passive"))
      (node (ref "RP4") (pin "1") (pinfunction "TOP_1") (pintype "passive"))
      (node (ref "U2") (pin "1") (pinfunction "OUT1_1") (pintype "passive"))
    )
    (net (code "32") (name "Net-(RP3-TAP)") (class "Default")
      (node (ref "R23") (pin "2") (pinfunction "2_2") (pintype "passive"))
      (node (ref "RP3") (pin "3") (pinfunction "TAP_3") (pintype "passive"))
      (node (ref "U2") (pin "5") (pinfunction "IN+_5") (pintype "passive"))
    )
    (net (code "33") (name "Net-(RP3-TOP)") (class "Default")
      (node (ref "R12") (pin "2") (pinfunction "2_2") (pintype "passive"))
      (node (ref "R2") (pin "1") (pinfunction "1_1") (pintype "passive"))
      (node (ref "RP3") (pin "1") (pinfunction "TOP_1") (pintype "passive"))
      (node (ref "U1") (pin "1") (pinfunction "OUT1_1") (pintype "passive"))
      (node (ref "U1") (pin "2") (pinfunction "IN-_2") (pintype "passive"))
    )
    (net (code "34") (name "Net-(RP4-BOT)") (class "Default")
      (node (ref "R14") (pin "2") (pinfunction "2_2") (pintype "passive"))
      (node (ref "R5") (pin "2") (pinfunction "2_2") (pintype "passive"))
      (node (ref "R6") (pin "1") (pinfunction "1_1") (pintype "passive"))
      (node (ref "RP4") (pin "2") (pinfunction "BOT_2") (pintype "passive"))
      (node (ref "RP5") (pin "1") (pinfunction "TOP_1") (pintype "passive"))
      (node (ref "U3") (pin "1") (pinfunction "OUT1_1") (pintype "passive"))
    )
    (net (code "35") (name "Net-(RP4-TAP)") (class "Default")
      (node (ref "R26") (pin "2") (pinfunction "2_2") (pintype "passive"))
      (node (ref "RP4") (pin "3") (pinfunction "TAP_3") (pintype "passive"))
      (node (ref "U3") (pin "5") (pinfunction "IN+_5") (pintype "passive"))
    )
    (net (code "36") (name "Net-(RP5-BOT)") (class "Default")
      (node (ref "R7") (pin "2") (pinfunction "2_2") (pintype "passive"))
      (node (ref "R8") (pin "1") (pinfunction "1_1") (pintype "passive"))
      (node (ref "RP5") (pin "2") (pinfunction "BOT_2") (pintype "passive"))
      (node (ref "U5") (pin "1") (pinfunction "OUT1_1") (pintype "passive"))
    )
    (net (code "37") (name "Net-(RP5-TAP)") (class "Default")
      (node (ref "R29") (pin "2") (pinfunction "2_2") (pintype "passive"))
      (node (ref "RP5") (pin "3") (pinfunction "TAP_3") (pintype "passive"))
      (node (ref "U5") (pin "5") (pinfunction "IN+_5") (pintype "passive"))
    )
    (net (code "38") (name "Net-(U1B-IN+)") (class "Default")
      (node (ref "R8") (pin "2") (pinfunction "2_2") (pintype "passive"))
      (node (ref "U1") (pin "5") (pinfunction "IN+_5") (pintype "passive"))
    )
    (net (code "39") (name "Net-(U2A-IN+)") (class "Default")
      (node (ref "C15") (pin "2") (pinfunction "2_2") (pintype "passive"))
      (node (ref "RP6") (pin "2") (pinfunction "2_2") (pintype "passive"))
      (node (ref "RP6") (pin "4") (pinfunction "4_4") (pintype "passive"))
      (node (ref "RP6") (pin "6") (pinfunction "6_6") (pintype "passive"))
      (node (ref "U2") (pin "3") (pinfunction "IN+_3") (pintype "passive"))
    )
    (net (code "40") (name "Net-(U2A-IN-)") (class "Default")
      (node (ref "R2") (pin "2") (pinfunction "2_2") (pintype "passive"))
      (node (ref "R3") (pin "1") (pinfunction "1_1") (pintype "passive"))
      (node (ref "U2") (pin "2") (pinfunction "IN-_2") (pintype "passive"))
    )
    (net (code "41") (name "Net-(U2B-IN-)") (class "Default")
      (node (ref "R17") (pin "2") (pinfunction "2_2") (pintype "passive"))
      (node (ref "R24") (pin "2") (pinfunction "2_2") (pintype "passive"))
      (node (ref "U2") (pin "6") (pinfunction "IN-_6") (pintype "passive"))
    )
    (net (code "42") (name "Net-(U2B-OUT2)") (class "Default")
      (node (ref "R17") (pin "1") (pinfunction "1_1") (pintype "passive"))
      (node (ref "R25") (pin "1") (pinfunction "1_1") (pintype "passive"))
      (node (ref "U2") (pin "7") (pinfunction "OUT2_7") (pintype "passive"))
    )
    (net (code "43") (name "Net-(U3A-IN+)") (class "Default")
      (node (ref "C16") (pin "2") (pinfunction "2_2") (pintype "passive"))
      (node (ref "RP7") (pin "2") (pinfunction "2_2") (pintype "passive"))
      (node (ref "RP7") (pin "4") (pinfunction "4_4") (pintype "passive"))
      (node (ref "RP7") (pin "6") (pinfunction "6_6") (pintype "passive"))
      (node (ref "U3") (pin "3") (pinfunction "IN+_3") (pintype "passive"))
    )
    (net (code "44") (name "Net-(U3A-IN-)") (class "Default")
      (node (ref "R4") (pin "2") (pinfunction "2_2") (pintype "passive"))
      (node (ref "R5") (pin "1") (pinfunction "1_1") (pintype "passive"))
      (node (ref "U3") (pin "2") (pinfunction "IN-_2") (pintype "passive"))
    )
    (net (code "45") (name "Net-(U3B-IN-)") (class "Default")
      (node (ref "R18") (pin "2") (pinfunction "2_2") (pintype "passive"))
      (node (ref "R27") (pin "2") (pinfunction "2_2") (pintype "passive"))
      (node (ref "U3") (pin "6") (pinfunction "IN-_6") (pintype "passive"))
    )
    (net (code "46") (name "Net-(U3B-OUT2)") (class "Default")
      (node (ref "R18") (pin "1") (pinfunction "1_1") (pintype "passive"))
      (node (ref "R28") (pin "1") (pinfunction "1_1") (pintype "passive"))
      (node (ref "U3") (pin "7") (pinfunction "OUT2_7") (pintype "passive"))
    )
    (net (code "47") (name "Net-(U5A-IN+)") (class "Default")
      (node (ref "C17") (pin "2") (pinfunction "2_2") (pintype "passive"))
      (node (ref "RP8") (pin "2") (pinfunction "2_2") (pintype "passive"))
      (node (ref "RP8") (pin "4") (pinfunction "4_4") (pintype "passive"))
      (node (ref "RP8") (pin "6") (pinfunction "6_6") (pintype "passive"))
      (node (ref "U5") (pin "3") (pinfunction "IN+_3") (pintype "passive"))
    )
    (net (code "48") (name "Net-(U5A-IN-)") (class "Default")
      (node (ref "R6") (pin "2") (pinfunction "2_2") (pintype "passive"))
      (node (ref "R7") (pin "1") (pinfunction "1_1") (pintype "passive"))
      (node (ref "U5") (pin "2") (pinfunction "IN-_2") (pintype "passive"))
    )
    (net (code "49") (name "Net-(U5B-IN-)") (class "Default")
      (node (ref "R19") (pin "2") (pinfunction "2_2") (pintype "passive"))
      (node (ref "R30") (pin "2") (pinfunction "2_2") (pintype "passive"))
      (node (ref "U5") (pin "6") (pinfunction "IN-_6") (pintype "passive"))
    )
    (net (code "50") (name "Net-(U5B-OUT2)") (class "Default")
      (node (ref "R19") (pin "1") (pinfunction "1_1") (pintype "passive"))
      (node (ref "R31") (pin "1") (pinfunction "1_1") (pintype "passive"))
      (node (ref "U5") (pin "7") (pinfunction "OUT2_7") (pintype "passive"))
    )
    (net (code "51") (name "V+") (class "Default")
      (node (ref "C11") (pin "2") (pinfunction "2_2") (pintype "passive"))
      (node (ref "C12") (pin "2") (pinfunction "2_2") (pintype "passive"))
      (node (ref "C13") (pin "2") (pinfunction "2_2") (pintype "passive"))
      (node (ref "C14") (pin "2") (pinfunction "2_2") (pintype "passive"))
      (node (ref "C30") (pin "1") (pinfunction "1_1") (pintype "passive"))
      (node (ref "R1") (pin "1") (pinfunction "1_1") (pintype "passive"))
      (node (ref "U1") (pin "8") (pinfunction "VCC+_8") (pintype "passive"))
      (node (ref "U2") (pin "8") (pinfunction "VCC+_8") (pintype "passive"))
      (node (ref "U3") (pin "8") (pinfunction "VCC+_8") (pintype "passive"))
      (node (ref "U5") (pin "8") (pinfunction "VCC+_8") (pintype "passive"))
    )
    (net (code "52") (name "V-") (class "Default")
      (node (ref "C18") (pin "1") (pinfunction "1_1") (pintype "passive"))
      (node (ref "C19") (pin "1") (pinfunction "1_1") (pintype "passive"))
      (node (ref "C20") (pin "1") (pinfunction "1_1") (pintype "passive"))
      (node (ref "C21") (pin "1") (pinfunction "1_1") (pintype "passive"))
      (node (ref "C31") (pin "2") (pinfunction "2_2") (pintype "passive"))
      (node (ref "R10") (pin "1") (pinfunction "1_1") (pintype "passive"))
      (node (ref "U1") (pin "4") (pinfunction "VCC-_4") (pintype "passive"))
      (node (ref "U2") (pin "4") (pinfunction "VCC-_4") (pintype "passive"))
      (node (ref "U3") (pin "4") (pinfunction "VCC-_4") (pintype "passive"))
      (node (ref "U5") (pin "4") (pinfunction "VCC-_4") (pintype "passive"))
    )
  )
)
